# RadioMusic_F.net
KiCad netlist of a schematic drawn in EAGLE
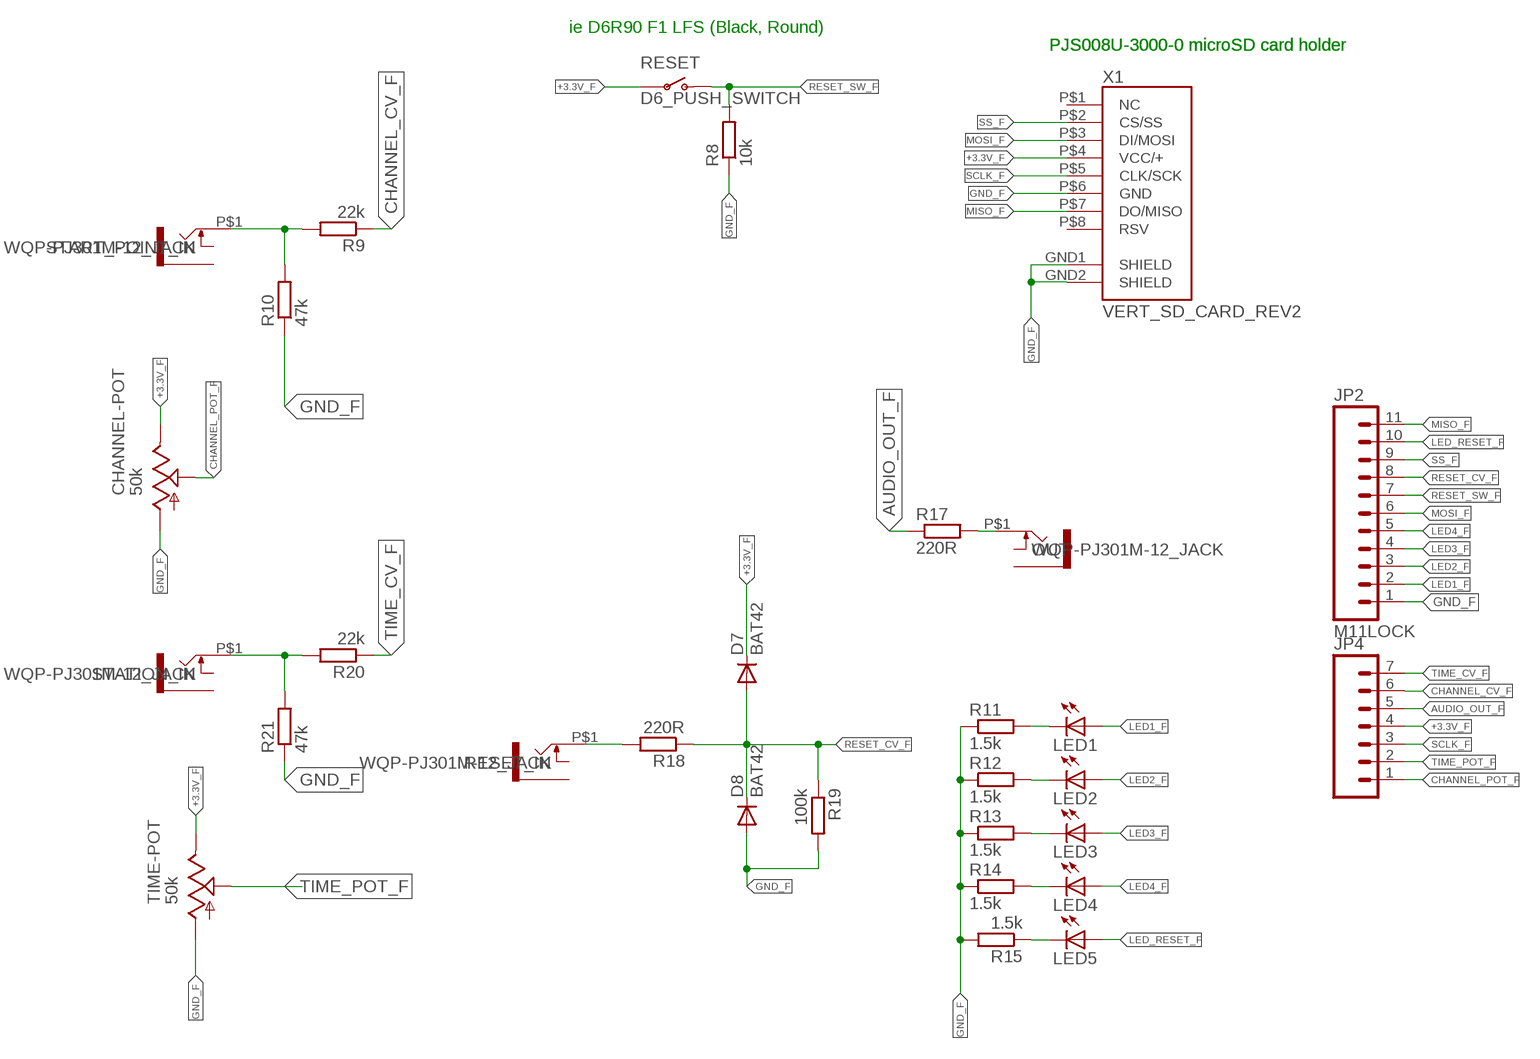
[diagram p0: schematic, sheet 1]

(export (version "E")
  (design (tool "Eeschema 10.0.6"))
  (components
    (comp (ref "CHANNEL-POT")
      (value "50k")
      (footprint "eagle-import:EVUF")
      (libsource (lib "eagle-import") (part "ALPHA-9MMAF2"))
    )
    (comp (ref "D7")
      (value "BAT42")
      (footprint "eagle-import:DO34-7")
      (libsource (lib "eagle-import") (part "BAT81"))
    )
    (comp (ref "D8")
      (value "BAT42")
      (footprint "eagle-import:DO34-7")
      (libsource (lib "eagle-import") (part "BAT81"))
    )
    (comp (ref "JP2")
      (value "M11LOCK")
      (footprint "eagle-import:1X11_LOCK")
      (libsource (lib "eagle-import") (part "M11LOCK"))
    )
    (comp (ref "JP4")
      (value "M07LOCK")
      (footprint "eagle-import:1X07_LOCK")
      (libsource (lib "eagle-import") (part "M07LOCK"))
    )
    (comp (ref "LED1")
      (value "LED3MM")
      (footprint "eagle-import:LED3MM")
      (libsource (lib "eagle-import") (part "LED3MM"))
    )
    (comp (ref "LED2")
      (value "LED3MM")
      (footprint "eagle-import:LED3MM")
      (libsource (lib "eagle-import") (part "LED3MM"))
    )
    (comp (ref "LED3")
      (value "LED3MM")
      (footprint "eagle-import:LED3MM")
      (libsource (lib "eagle-import") (part "LED3MM"))
    )
    (comp (ref "LED4")
      (value "LED3MM")
      (footprint "eagle-import:LED3MM")
      (libsource (lib "eagle-import") (part "LED3MM"))
    )
    (comp (ref "LED5")
      (value "LED3MM")
      (footprint "eagle-import:LED3MM")
      (libsource (lib "eagle-import") (part "LED3MM"))
    )
    (comp (ref "OUT")
      (value "WQP-PJ301M-12_JACK")
      (footprint "eagle-import:WQP-PJ301M-12_JACK")
      (libsource (lib "eagle-import") (part "WQP-PJ301M-12_JACK"))
    )
    (comp (ref "R8")
      (value "10k")
      (footprint "eagle-import:0207_10")
      (libsource (lib "eagle-import") (part "R-EU_STANDARD_RESISTOR"))
    )
    (comp (ref "R9")
      (value "22k")
      (footprint "eagle-import:0207_10")
      (libsource (lib "eagle-import") (part "R-EU_STANDARD_RESISTOR"))
    )
    (comp (ref "R10")
      (value "47k")
      (footprint "eagle-import:0207_10")
      (libsource (lib "eagle-import") (part "R-EU_STANDARD_RESISTOR"))
    )
    (comp (ref "R11")
      (value "1.5k")
      (footprint "eagle-import:0207_10")
      (libsource (lib "eagle-import") (part "R-EU_STANDARD_RESISTOR"))
    )
    (comp (ref "R12")
      (value "1.5k")
      (footprint "eagle-import:0207_10")
      (libsource (lib "eagle-import") (part "R-EU_STANDARD_RESISTOR"))
    )
    (comp (ref "R13")
      (value "1.5k")
      (footprint "eagle-import:0207_10")
      (libsource (lib "eagle-import") (part "R-EU_STANDARD_RESISTOR"))
    )
    (comp (ref "R14")
      (value "1.5k")
      (footprint "eagle-import:0207_10")
      (libsource (lib "eagle-import") (part "R-EU_STANDARD_RESISTOR"))
    )
    (comp (ref "R15")
      (value "1.5k")
      (footprint "eagle-import:0207_10")
      (libsource (lib "eagle-import") (part "R-EU_STANDARD_RESISTOR"))
    )
    (comp (ref "R17")
      (value "220R")
      (footprint "eagle-import:0207_10")
      (libsource (lib "eagle-import") (part "R-EU_STANDARD_RESISTOR"))
    )
    (comp (ref "R18")
      (value "220R")
      (footprint "eagle-import:0207_10")
      (libsource (lib "eagle-import") (part "R-EU_STANDARD_RESISTOR"))
    )
    (comp (ref "R19")
      (value "100k")
      (footprint "eagle-import:0207_10")
      (libsource (lib "eagle-import") (part "R-EU_STANDARD_RESISTOR"))
    )
    (comp (ref "R20")
      (value "22k")
      (footprint "eagle-import:0207_10")
      (libsource (lib "eagle-import") (part "R-EU_STANDARD_RESISTOR"))
    )
    (comp (ref "R21")
      (value "47k")
      (footprint "eagle-import:0207_10")
      (libsource (lib "eagle-import") (part "R-EU_STANDARD_RESISTOR"))
    )
    (comp (ref "RESET")
      (value "D6_PUSH_SWITCH")
      (footprint "eagle-import:D6_BUTTON_RND")
      (libsource (lib "eagle-import") (part "D6_PUSH_SWITCH"))
    )
    (comp (ref "RESET_IN")
      (value "WQP-PJ301M-12_JACK")
      (footprint "eagle-import:WQP-PJ301M-12_JACK")
      (libsource (lib "eagle-import") (part "WQP-PJ301M-12_JACK"))
    )
    (comp (ref "START_POINT_IN")
      (value "WQP-PJ301M-12_JACK")
      (footprint "eagle-import:WQP-PJ301M-12_JACK")
      (libsource (lib "eagle-import") (part "WQP-PJ301M-12_JACK"))
    )
    (comp (ref "STATION_IN")
      (value "WQP-PJ301M-12_JACK")
      (footprint "eagle-import:WQP-PJ301M-12_JACK")
      (libsource (lib "eagle-import") (part "WQP-PJ301M-12_JACK"))
    )
    (comp (ref "TIME-POT")
      (value "50k")
      (footprint "eagle-import:EVUF")
      (libsource (lib "eagle-import") (part "ALPHA-9MMAF2"))
    )
    (comp (ref "X1")
      (value "VERT_SD_CARD_REV2")
      (footprint "eagle-import:VERT_MICROSD_REV2")
      (libsource (lib "eagle-import") (part "VERT_SD_CARD_REV2"))
    )
  )
  (nets
    (net (code "1") (name "+3.3V_F") (class "Default")
      (node (ref "CHANNEL-POT") (pin "3") (pinfunction "E_3") (pintype "passive"))
      (node (ref "D7") (pin "C") (pinfunction "C_C") (pintype "passive"))
      (node (ref "JP4") (pin "4") (pinfunction "4_4") (pintype "passive"))
      (node (ref "RESET") (pin "P$3") (pinfunction "P_P$3") (pintype "passive"))
      (node (ref "RESET") (pin "P$4") (pinfunction "P_P$4") (pintype "passive"))
      (node (ref "TIME-POT") (pin "3") (pinfunction "E_3") (pintype "passive"))
      (node (ref "X1") (pin "P$4") (pinfunction "VCC/+_P$4") (pintype "bidirectional"))
    )
    (net (code "2") (name "AUDIO_OUT_F") (class "Default")
      (node (ref "JP4") (pin "5") (pinfunction "5_5") (pintype "passive"))
      (node (ref "R17") (pin "1") (pinfunction "1_1") (pintype "passive"))
    )
    (net (code "3") (name "CHANNEL_CV_F") (class "Default")
      (node (ref "JP4") (pin "6") (pinfunction "6_6") (pintype "passive"))
      (node (ref "R9") (pin "1") (pinfunction "1_1") (pintype "passive"))
    )
    (net (code "4") (name "CHANNEL_POT_F") (class "Default")
      (node (ref "CHANNEL-POT") (pin "2") (pinfunction "S_2") (pintype "passive"))
      (node (ref "JP4") (pin "1") (pinfunction "1_1") (pintype "passive"))
    )
    (net (code "5") (name "GND_F") (class "Default")
      (node (ref "CHANNEL-POT") (pin "1") (pinfunction "A_1") (pintype "passive"))
      (node (ref "D8") (pin "A") (pinfunction "A_A") (pintype "passive"))
      (node (ref "JP2") (pin "1") (pinfunction "1_1") (pintype "passive"))
      (node (ref "R10") (pin "1") (pinfunction "1_1") (pintype "passive"))
      (node (ref "R11") (pin "1") (pinfunction "1_1") (pintype "passive"))
      (node (ref "R12") (pin "1") (pinfunction "1_1") (pintype "passive"))
      (node (ref "R13") (pin "1") (pinfunction "1_1") (pintype "passive"))
      (node (ref "R14") (pin "1") (pinfunction "1_1") (pintype "passive"))
      (node (ref "R15") (pin "2") (pinfunction "2_2") (pintype "passive"))
      (node (ref "R19") (pin "2") (pinfunction "2_2") (pintype "passive"))
      (node (ref "R21") (pin "1") (pinfunction "1_1") (pintype "passive"))
      (node (ref "R8") (pin "1") (pinfunction "1_1") (pintype "passive"))
      (node (ref "TIME-POT") (pin "1") (pinfunction "A_1") (pintype "passive"))
      (node (ref "X1") (pin "GND1") (pinfunction "SHIELD_GND1") (pintype "bidirectional"))
      (node (ref "X1") (pin "GND2") (pinfunction "SHIELD_GND2") (pintype "bidirectional"))
      (node (ref "X1") (pin "P$6") (pinfunction "GND_P$6") (pintype "bidirectional"))
    )
    (net (code "6") (name "LED1_F") (class "Default")
      (node (ref "JP2") (pin "2") (pinfunction "2_2") (pintype "passive"))
      (node (ref "LED1") (pin "A") (pinfunction "A_A") (pintype "passive"))
    )
    (net (code "7") (name "LED2_F") (class "Default")
      (node (ref "JP2") (pin "3") (pinfunction "3_3") (pintype "passive"))
      (node (ref "LED2") (pin "A") (pinfunction "A_A") (pintype "passive"))
    )
    (net (code "8") (name "LED3_F") (class "Default")
      (node (ref "JP2") (pin "4") (pinfunction "4_4") (pintype "passive"))
      (node (ref "LED3") (pin "A") (pinfunction "A_A") (pintype "passive"))
    )
    (net (code "9") (name "LED4_F") (class "Default")
      (node (ref "JP2") (pin "5") (pinfunction "5_5") (pintype "passive"))
      (node (ref "LED4") (pin "A") (pinfunction "A_A") (pintype "passive"))
    )
    (net (code "10") (name "LED_RESET_F") (class "Default")
      (node (ref "JP2") (pin "10") (pinfunction "10_10") (pintype "passive"))
      (node (ref "LED5") (pin "A") (pinfunction "A_A") (pintype "passive"))
    )
    (net (code "11") (name "MISO_F") (class "Default")
      (node (ref "JP2") (pin "11") (pinfunction "11_11") (pintype "passive"))
      (node (ref "X1") (pin "P$7") (pinfunction "DO/MISO_P$7") (pintype "bidirectional"))
    )
    (net (code "12") (name "MOSI_F") (class "Default")
      (node (ref "JP2") (pin "6") (pinfunction "6_6") (pintype "passive"))
      (node (ref "X1") (pin "P$3") (pinfunction "DI/MOSI_P$3") (pintype "bidirectional"))
    )
    (net (code "13") (name "Net-(LED1-C)") (class "Default")
      (node (ref "LED1") (pin "K") (pinfunction "C_K") (pintype "passive"))
      (node (ref "R11") (pin "2") (pinfunction "2_2") (pintype "passive"))
    )
    (net (code "14") (name "Net-(LED2-C)") (class "Default")
      (node (ref "LED2") (pin "K") (pinfunction "C_K") (pintype "passive"))
      (node (ref "R12") (pin "2") (pinfunction "2_2") (pintype "passive"))
    )
    (net (code "15") (name "Net-(LED3-C)") (class "Default")
      (node (ref "LED3") (pin "K") (pinfunction "C_K") (pintype "passive"))
      (node (ref "R13") (pin "2") (pinfunction "2_2") (pintype "passive"))
    )
    (net (code "16") (name "Net-(LED4-C)") (class "Default")
      (node (ref "LED4") (pin "K") (pinfunction "C_K") (pintype "passive"))
      (node (ref "R14") (pin "2") (pinfunction "2_2") (pintype "passive"))
    )
    (net (code "17") (name "Net-(LED5-C)") (class "Default")
      (node (ref "LED5") (pin "K") (pinfunction "C_K") (pintype "passive"))
      (node (ref "R15") (pin "1") (pinfunction "1_1") (pintype "passive"))
    )
    (net (code "18") (name "Net-(OUT-2)") (class "Default")
      (node (ref "OUT") (pin "P$1") (pinfunction "2_P$1") (pintype "passive"))
      (node (ref "R17") (pin "2") (pinfunction "2_2") (pintype "passive"))
    )
    (net (code "19") (name "Net-(RESET_IN-2)") (class "Default")
      (node (ref "R18") (pin "2") (pinfunction "2_2") (pintype "passive"))
      (node (ref "RESET_IN") (pin "P$1") (pinfunction "2_P$1") (pintype "passive"))
    )
    (net (code "20") (name "Net-(START_POINT_IN-2)") (class "Default")
      (node (ref "R10") (pin "2") (pinfunction "2_2") (pintype "passive"))
      (node (ref "R9") (pin "2") (pinfunction "2_2") (pintype "passive"))
      (node (ref "START_POINT_IN") (pin "P$1") (pinfunction "2_P$1") (pintype "passive"))
    )
    (net (code "21") (name "Net-(STATION_IN-2)") (class "Default")
      (node (ref "R20") (pin "2") (pinfunction "2_2") (pintype "passive"))
      (node (ref "R21") (pin "2") (pinfunction "2_2") (pintype "passive"))
      (node (ref "STATION_IN") (pin "P$1") (pinfunction "2_P$1") (pintype "passive"))
    )
    (net (code "22") (name "RESET_CV_F") (class "Default")
      (node (ref "D7") (pin "A") (pinfunction "A_A") (pintype "passive"))
      (node (ref "D8") (pin "C") (pinfunction "C_C") (pintype "passive"))
      (node (ref "JP2") (pin "8") (pinfunction "8_8") (pintype "passive"))
      (node (ref "R18") (pin "1") (pinfunction "1_1") (pintype "passive"))
      (node (ref "R19") (pin "1") (pinfunction "1_1") (pintype "passive"))
    )
    (net (code "23") (name "RESET_SW_F") (class "Default")
      (node (ref "JP2") (pin "7") (pinfunction "7_7") (pintype "passive"))
      (node (ref "R8") (pin "2") (pinfunction "2_2") (pintype "passive"))
      (node (ref "RESET") (pin "P$1") (pinfunction "O_P$1") (pintype "passive"))
      (node (ref "RESET") (pin "P$2") (pinfunction "O_P$2") (pintype "passive"))
    )
    (net (code "24") (name "SCLK_F") (class "Default")
      (node (ref "JP4") (pin "3") (pinfunction "3_3") (pintype "passive"))
      (node (ref "X1") (pin "P$5") (pinfunction "CLK/SCK_P$5") (pintype "bidirectional"))
    )
    (net (code "25") (name "SS_F") (class "Default")
      (node (ref "JP2") (pin "9") (pinfunction "9_9") (pintype "passive"))
      (node (ref "X1") (pin "P$2") (pinfunction "CS/SS_P$2") (pintype "bidirectional"))
    )
    (net (code "26") (name "TIME_CV_F") (class "Default")
      (node (ref "JP4") (pin "7") (pinfunction "7_7") (pintype "passive"))
      (node (ref "R20") (pin "1") (pinfunction "1_1") (pintype "passive"))
    )
    (net (code "27") (name "TIME_POT_F") (class "Default")
      (node (ref "JP4") (pin "2") (pinfunction "2_2") (pintype "passive"))
      (node (ref "TIME-POT") (pin "2") (pinfunction "S_2") (pintype "passive"))
    )
    (net (code "28") (name "unconnected-(X1-NC-PadP$1)") (class "Default")
      (node (ref "X1") (pin "P$1") (pinfunction "NC_P$1") (pintype "bidirectional"))
    )
    (net (code "29") (name "unconnected-(X1-RSV-PadP$8)") (class "Default")
      (node (ref "X1") (pin "P$8") (pinfunction "RSV_P$8") (pintype "bidirectional"))
    )
  )
)
